# Current_Sensor.net
KiCad netlist of a schematic drawn in Altium Designer
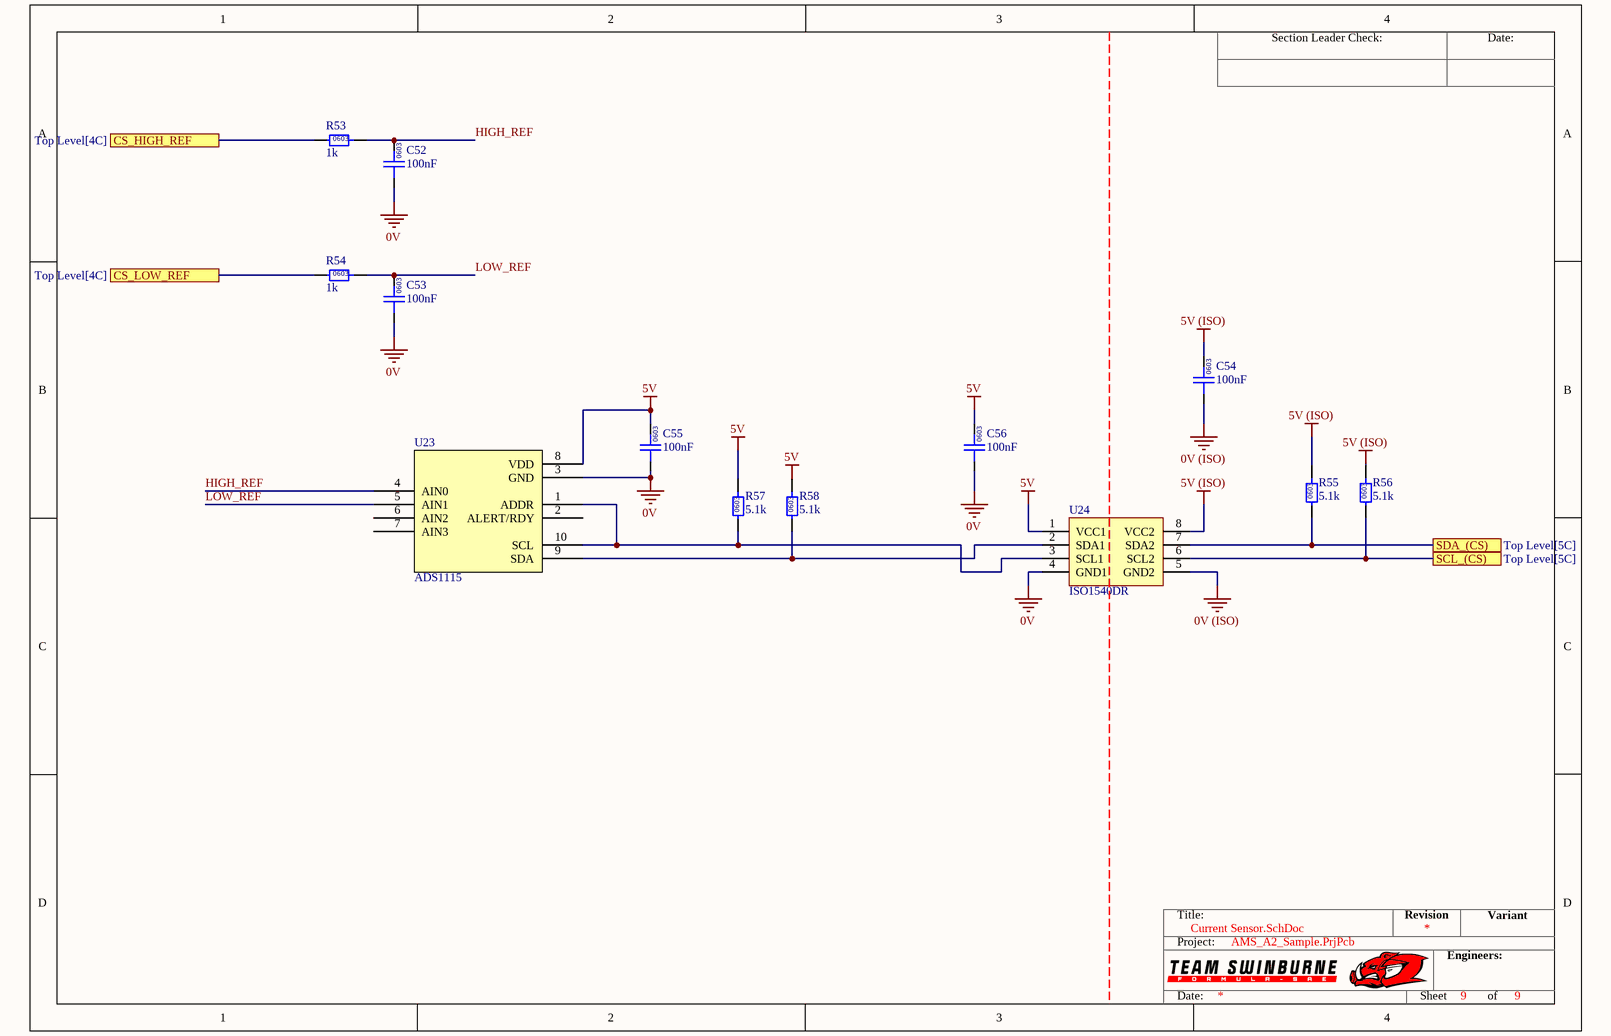
[diagram p0: Current Sensor.SchDoc]

(export (version "E")
  (design (tool "Eeschema 10.0.6"))
  (components
    (comp (ref "C52")
      (value "100nF")
      (footprint "0603")
      (fields
        (field (name "PART NUMBER") "GCM188L81H104KA57D")
        (field (name "MANUFACTURER") "muRata")
        (field (name "TOLERANCE") "±10%")
      )
      (libsource (lib "ts_standard_library") (part "Capacitor 0603"))
    )
    (comp (ref "C53")
      (value "100nF")
      (footprint "0603")
      (fields
        (field (name "PART NUMBER") "GCM188L81H104KA57D")
        (field (name "MANUFACTURER") "muRata")
        (field (name "TOLERANCE") "±10%")
      )
      (libsource (lib "ts_standard_library") (part "Capacitor 0603"))
    )
    (comp (ref "C54")
      (value "100nF")
      (footprint "0603")
      (fields
        (field (name "PART NUMBER") "GCM188L81H104KA57D")
        (field (name "MANUFACTURER") "muRata")
        (field (name "TOLERANCE") "±10%")
      )
      (libsource (lib "ts_standard_library") (part "Capacitor 0603"))
    )
    (comp (ref "C55")
      (value "100nF")
      (footprint "0603")
      (fields
        (field (name "PART NUMBER") "GCM188L81H104KA57D")
        (field (name "MANUFACTURER") "muRata")
        (field (name "TOLERANCE") "±10%")
      )
      (libsource (lib "ts_standard_library") (part "Capacitor 0603"))
    )
    (comp (ref "C56")
      (value "100nF")
      (footprint "0603")
      (fields
        (field (name "PART NUMBER") "GCM188L81H104KA57D")
        (field (name "MANUFACTURER") "muRata")
        (field (name "TOLERANCE") "±10%")
      )
      (libsource (lib "ts_standard_library") (part "Capacitor 0603"))
    )
    (comp (ref "R53")
      (value "1k")
      (footprint "0603")
      (fields
        (field (name "PART NUMBER") "RC0603FR-071KL")
        (field (name "MANUFACTURER") "YAGEO")
        (field (name "TOLERANCE") "0.01")
      )
      (libsource (lib "ts_standard_library") (part "Resistor 0603"))
    )
    (comp (ref "R54")
      (value "1k")
      (footprint "0603")
      (fields
        (field (name "PART NUMBER") "RC0603FR-071KL")
        (field (name "MANUFACTURER") "YAGEO")
        (field (name "TOLERANCE") "0.01")
      )
      (libsource (lib "ts_standard_library") (part "Resistor 0603"))
    )
    (comp (ref "R55")
      (value "5.1k")
      (footprint "0603")
      (fields
        (field (name "PART NUMBER") "RC0603JR-075K1L")
        (field (name "MANUFACTURER") "YAGEO")
        (field (name "TOLERANCE") "0.01")
      )
      (libsource (lib "ts_standard_library") (part "Resistor 0603"))
    )
    (comp (ref "R56")
      (value "5.1k")
      (footprint "0603")
      (fields
        (field (name "PART NUMBER") "RC0603JR-075K1L")
        (field (name "MANUFACTURER") "YAGEO")
        (field (name "TOLERANCE") "0.01")
      )
      (libsource (lib "ts_standard_library") (part "Resistor 0603"))
    )
    (comp (ref "R57")
      (value "5.1k")
      (footprint "0603")
      (fields
        (field (name "PART NUMBER") "RC0603JR-075K1L")
        (field (name "MANUFACTURER") "YAGEO")
        (field (name "TOLERANCE") "0.01")
      )
      (libsource (lib "ts_standard_library") (part "Resistor 0603"))
    )
    (comp (ref "R58")
      (value "5.1k")
      (footprint "0603")
      (fields
        (field (name "PART NUMBER") "RC0603JR-075K1L")
        (field (name "MANUFACTURER") "YAGEO")
        (field (name "TOLERANCE") "0.01")
      )
      (libsource (lib "ts_standard_library") (part "Resistor 0603"))
    )
    (comp (ref "U23")
      (value "ADS1115")
      (footprint "TI 10-VSSOP")
      (description "16 Bit Analog to Digital Converter 2, 4 Input 1 Sigma-Delta 10-VSSOP")
      (fields
        (field (name "MANUFACTURER") "Texas Instruments")
        (field (name "DIGIKEY PART NUMBER") "296-38849-1-ND")
      )
      (libsource (lib "ts_standard_library") (part "ADS1115"))
    )
    (comp (ref "U24")
      (value "ISO1540DR")
      (footprint "TI 8-SOIC")
      (description "I2C Digital Isolator (Multichannel)")
      (fields
        (field (name "MANUFACTURER") "Texas Instruments")
        (field (name "DIGIKEY PART NUMBER") "296-34871-1-ND")
      )
      (libsource (lib "ts_20-standard-library") (part "ISO1540DR"))
    )
  )
  (nets
    (net (code "1") (name "/CS_HIGH_REF") (class "Default")
      (node (ref "R53") (pin "1") (pinfunction "1_1") (pintype "passive"))
    )
    (net (code "2") (name "/CS_LOW_REF") (class "Default")
      (node (ref "R54") (pin "1") (pinfunction "1_1") (pintype "passive"))
    )
    (net (code "3") (name "/HIGH_REF") (class "Default")
      (node (ref "C52") (pin "2") (pinfunction "2_2") (pintype "passive"))
      (node (ref "R53") (pin "2") (pinfunction "2_2") (pintype "passive"))
      (node (ref "U23") (pin "4") (pinfunction "AIN0_4") (pintype "passive"))
    )
    (net (code "4") (name "/LOW_REF") (class "Default")
      (node (ref "C53") (pin "2") (pinfunction "2_2") (pintype "passive"))
      (node (ref "R54") (pin "2") (pinfunction "2_2") (pintype "passive"))
      (node (ref "U23") (pin "5") (pinfunction "AIN1_5") (pintype "passive"))
    )
    (net (code "5") (name "/SCL_(CS)") (class "Default")
      (node (ref "R56") (pin "1") (pinfunction "1_1") (pintype "passive"))
      (node (ref "U24") (pin "6") (pinfunction "SCL2_6") (pintype "power_in"))
    )
    (net (code "6") (name "/SDA_(CS)") (class "Default")
      (node (ref "R55") (pin "1") (pinfunction "1_1") (pintype "passive"))
      (node (ref "U24") (pin "7") (pinfunction "SDA2_7") (pintype "power_in"))
    )
    (net (code "7") (name "0V") (class "Default")
      (node (ref "C52") (pin "1") (pinfunction "1_1") (pintype "passive"))
      (node (ref "C53") (pin "1") (pinfunction "1_1") (pintype "passive"))
      (node (ref "C55") (pin "1") (pinfunction "1_1") (pintype "passive"))
      (node (ref "C56") (pin "1") (pinfunction "1_1") (pintype "passive"))
      (node (ref "U23") (pin "3") (pinfunction "GND_3") (pintype "passive"))
      (node (ref "U24") (pin "4") (pinfunction "GND1_4") (pintype "power_in"))
    )
    (net (code "8") (name "0V (ISO)") (class "Default")
      (node (ref "C54") (pin "1") (pinfunction "1_1") (pintype "passive"))
      (node (ref "U24") (pin "5") (pinfunction "GND2_5") (pintype "power_in"))
    )
    (net (code "9") (name "5V") (class "Default")
      (node (ref "C55") (pin "2") (pinfunction "2_2") (pintype "passive"))
      (node (ref "C56") (pin "2") (pinfunction "2_2") (pintype "passive"))
      (node (ref "R57") (pin "2") (pinfunction "2_2") (pintype "passive"))
      (node (ref "R58") (pin "2") (pinfunction "2_2") (pintype "passive"))
      (node (ref "U23") (pin "8") (pinfunction "VDD_8") (pintype "passive"))
      (node (ref "U24") (pin "1") (pinfunction "VCC1_1") (pintype "power_in"))
    )
    (net (code "10") (name "5V (ISO)") (class "Default")
      (node (ref "C54") (pin "2") (pinfunction "2_2") (pintype "passive"))
      (node (ref "R55") (pin "2") (pinfunction "2_2") (pintype "passive"))
      (node (ref "R56") (pin "2") (pinfunction "2_2") (pintype "passive"))
      (node (ref "U24") (pin "8") (pinfunction "VCC2_8") (pintype "power_in"))
    )
    (net (code "11") (name "Net-(U23-ADDR)") (class "Default")
      (node (ref "R57") (pin "1") (pinfunction "1_1") (pintype "passive"))
      (node (ref "U23") (pin "1") (pinfunction "ADDR_1") (pintype "passive"))
      (node (ref "U23") (pin "10") (pinfunction "SCL_10") (pintype "passive"))
      (node (ref "U24") (pin "3") (pinfunction "SCL1_3") (pintype "power_in"))
    )
    (net (code "12") (name "Net-(U23-SDA)") (class "Default")
      (node (ref "R58") (pin "1") (pinfunction "1_1") (pintype "passive"))
      (node (ref "U23") (pin "9") (pinfunction "SDA_9") (pintype "passive"))
      (node (ref "U24") (pin "2") (pinfunction "SDA1_2") (pintype "power_in"))
    )
    (net (code "13") (name "unconnected-(U23-AIN2-Pad6)") (class "Default")
      (node (ref "U23") (pin "6") (pinfunction "AIN2_6") (pintype "passive"))
    )
    (net (code "14") (name "unconnected-(U23-AIN3-Pad7)") (class "Default")
      (node (ref "U23") (pin "7") (pinfunction "AIN3_7") (pintype "passive"))
    )
    (net (code "15") (name "unconnected-(U23-ALERT{slash}RDY-Pad2)") (class "Default")
      (node (ref "U23") (pin "2") (pinfunction "ALERT/RDY_2") (pintype "passive"))
    )
  )
)
